# arduino.net
KiCad netlist of a schematic drawn in Altium Designer
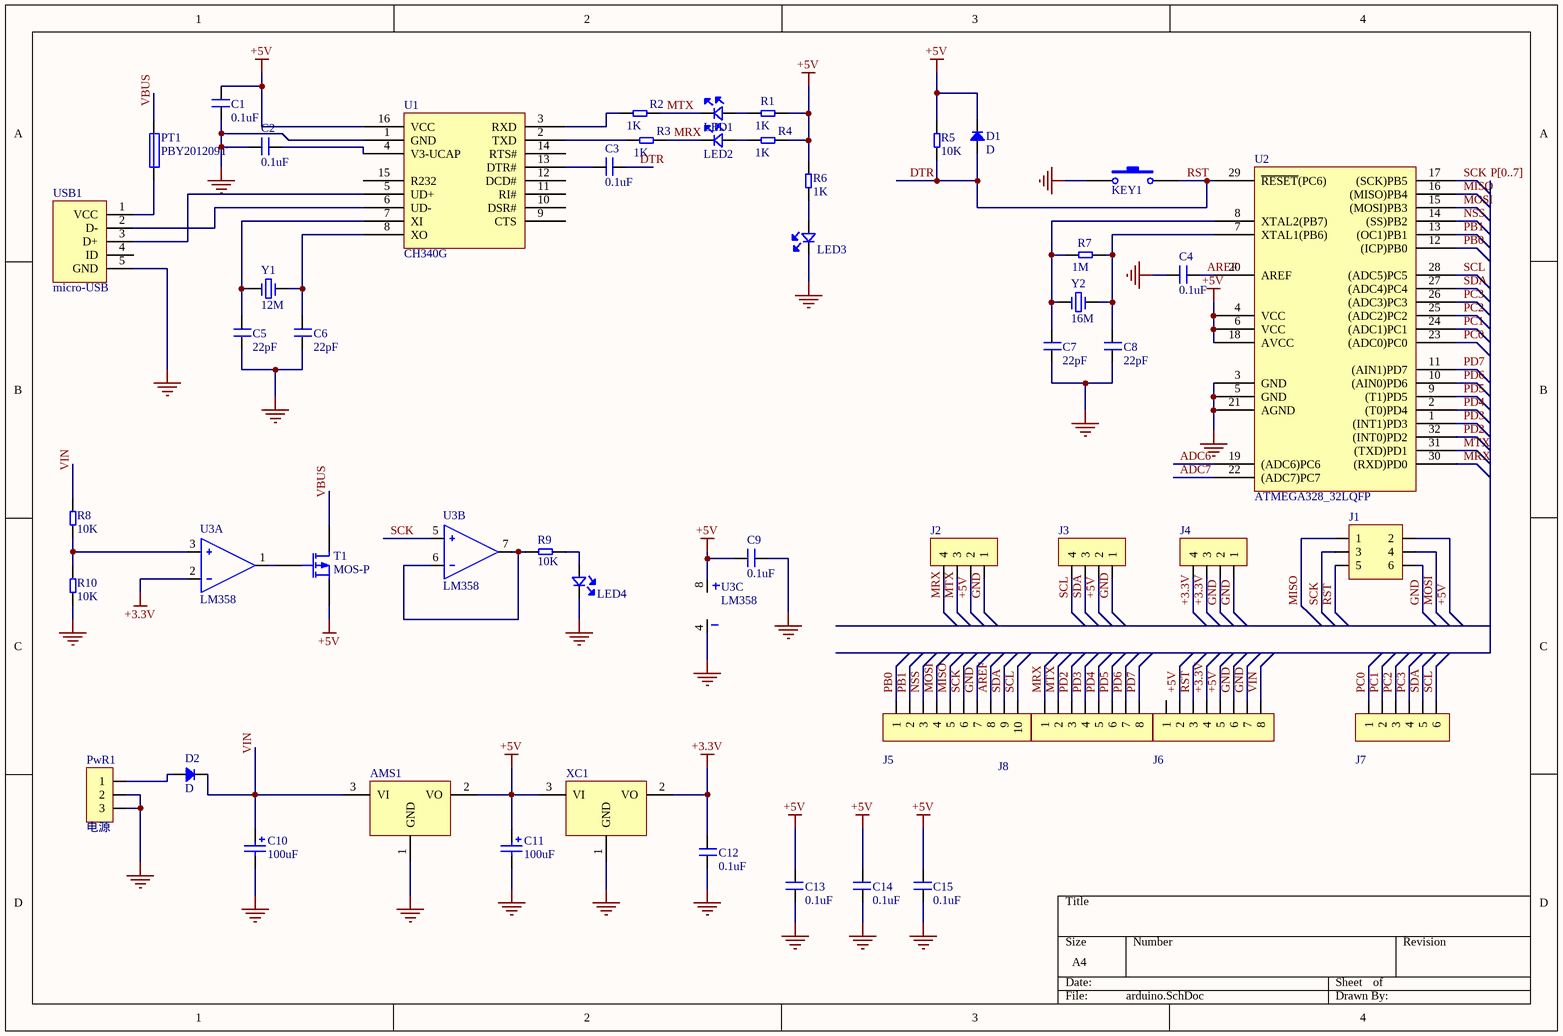
[diagram p0: arduino.SchDoc]

(export (version "E")
  (design (tool "Eeschema 10.0.6"))
  (components
    (comp (ref "AMS1")
      (value "AMS1117-5.0")
      (footprint "AMS1117-5.0")
      (libsource (lib "arduino") (part "AMS1117-5.0"))
    )
    (comp (ref "C1") (value "0.1uF") (footprint "0805C") (libsource (lib "arduino") (part "CAP")))
    (comp (ref "C2") (value "0.1uF") (footprint "0805C") (libsource (lib "arduino") (part "CAP")))
    (comp (ref "C3") (value "0.1uF") (footprint "0805C") (libsource (lib "arduino") (part "CAP")))
    (comp (ref "C4") (value "0.1uF") (footprint "0805C") (libsource (lib "arduino") (part "CAP")))
    (comp (ref "C5") (value "22pF") (footprint "0805C") (libsource (lib "arduino") (part "CAP")))
    (comp (ref "C6") (value "22pF") (footprint "0805C") (libsource (lib "arduino") (part "CAP")))
    (comp (ref "C7") (value "22pF") (footprint "0805C") (libsource (lib "arduino") (part "CAP")))
    (comp (ref "C8") (value "22pF") (footprint "0805C") (libsource (lib "arduino") (part "CAP")))
    (comp (ref "C9") (value "0.1uF") (footprint "0805C") (libsource (lib "arduino") (part "CAP")))
    (comp (ref "C10") (value "100uF") (footprint "CAP_P") (libsource (lib "arduino") (part "CAPP")))
    (comp (ref "C11") (value "100uF") (footprint "CAP_P") (libsource (lib "arduino") (part "CAPP")))
    (comp (ref "C12") (value "0.1uF") (footprint "0805C") (libsource (lib "arduino") (part "CAP")))
    (comp (ref "C13") (value "0.1uF") (footprint "0805C") (libsource (lib "arduino") (part "CAP")))
    (comp (ref "C14") (value "0.1uF") (footprint "0805C") (libsource (lib "arduino") (part "CAP")))
    (comp (ref "C15") (value "0.1uF") (footprint "0805C") (libsource (lib "arduino") (part "CAP")))
    (comp (ref "D1") (value "D") (footprint "1206D") (libsource (lib "arduino") (part "D")))
    (comp (ref "D2") (value "D") (footprint "1206D") (libsource (lib "arduino") (part "D")))
    (comp (ref "J1")
      (value "Header 2*3")
      (footprint "PIN2*3")
      (libsource (lib "arduino") (part "Header 2*3"))
    )
    (comp (ref "J2") (value "Header") (footprint "PIN4") (libsource (lib "arduino") (part "Header 4")))
    (comp (ref "J3") (value "Header") (footprint "PIN4") (libsource (lib "arduino") (part "Header 4")))
    (comp (ref "J4") (value "Header") (footprint "PIN4") (libsource (lib "arduino") (part "Header 4")))
    (comp (ref "J5") (value "Header 10") (footprint "PIN10") (libsource (lib "arduino") (part "Header 10")))
    (comp (ref "J6") (value "Header 8") (footprint "PIN8") (libsource (lib "arduino") (part "Header 8")))
    (comp (ref "J7") (value "Header 6") (footprint "PIN6") (libsource (lib "arduino") (part "Header 6")))
    (comp (ref "J8") (value "Header 8") (footprint "PIN8") (libsource (lib "arduino") (part "Header 8")))
    (comp (ref "KEY1") (value "KEY") (footprint "KEY") (libsource (lib "arduino") (part "KEY")))
    (comp (ref "LED1") (value "LED") (footprint "0805L") (libsource (lib "arduino") (part "LED")))
    (comp (ref "LED2") (value "LED") (footprint "0805L") (libsource (lib "arduino") (part "LED")))
    (comp (ref "LED3") (value "LED") (footprint "0805L") (libsource (lib "arduino") (part "LED")))
    (comp (ref "LED4") (value "LED") (footprint "0805L") (libsource (lib "arduino") (part "LED")))
    (comp (ref "PT1") (value "PBY201209T") (footprint "PT") (libsource (lib "arduino") (part "PT")))
    (comp (ref "PwR1") (value "电源") (footprint "DC005") (libsource (lib "arduino") (part "PwR")))
    (comp (ref "R1") (value "1K") (footprint "0805R") (libsource (lib "arduino") (part "RES")))
    (comp (ref "R2") (value "1K") (footprint "0805R") (libsource (lib "arduino") (part "RES")))
    (comp (ref "R3") (value "1K") (footprint "0805R") (libsource (lib "arduino") (part "RES")))
    (comp (ref "R4") (value "1K") (footprint "0805R") (libsource (lib "arduino") (part "RES")))
    (comp (ref "R5") (value "10K") (footprint "0805R") (libsource (lib "arduino") (part "RES")))
    (comp (ref "R6") (value "1K") (footprint "0805R") (libsource (lib "arduino") (part "RES")))
    (comp (ref "R7") (value "1M") (footprint "0805R") (libsource (lib "arduino") (part "RES")))
    (comp (ref "R8") (value "10K") (footprint "0805R") (libsource (lib "arduino") (part "RES")))
    (comp (ref "R9") (value "10K") (footprint "0805R") (libsource (lib "arduino") (part "RES")))
    (comp (ref "R10") (value "10K") (footprint "0805R") (libsource (lib "arduino") (part "RES")))
    (comp (ref "T1") (value "MOS-P") (footprint "SI2301") (libsource (lib "arduino") (part "MOS-P")))
    (comp (ref "U1") (value "CH340G") (footprint "CH340G") (libsource (lib "arduino") (part "CH340G")))
    (comp (ref "U2")
      (value "ATMEGA328_32LQFP")
      (footprint "ATMEGA328P-AU")
      (libsource (lib "arduino") (part "ATMEGA328_32LQFP"))
    )
    (comp (ref "U3") (value "LM358") (footprint "LM358") (libsource (lib "arduino") (part "LM358")))
    (comp (ref "USB1")
      (value "micro-USB")
      (footprint "micro-usb")
      (libsource (lib "arduino") (part "micro-USB"))
    )
    (comp (ref "XC1")
      (value "XC6206P332")
      (footprint "XC626P332")
      (libsource (lib "arduino") (part "XC6206P332"))
    )
    (comp (ref "Y1") (value "12M") (footprint "CRYSTAL") (libsource (lib "arduino") (part "CRYSTAL")))
    (comp (ref "Y2") (value "16M") (footprint "CRYSTAL") (libsource (lib "arduino") (part "CRYSTAL")))
  )
  (nets
    (net (code "9") (name "+3.3V") (class "Default")
      (node (ref "C12") (pin "1") (pinfunction "1_1") (pintype "passive"))
      (node (ref "J4") (pin "3") (pinfunction "3_3") (pintype "passive"))
      (node (ref "J4") (pin "4") (pinfunction "4_4") (pintype "passive"))
      (node (ref "J6") (pin "4") (pinfunction "4_4") (pintype "passive"))
      (node (ref "U3") (pin "2") (pinfunction "2_2") (pintype "passive"))
      (node (ref "XC1") (pin "2") (pinfunction "VO_2") (pintype "passive"))
    )
    (net (code "10") (name "+5V") (class "Default")
      (node (ref "AMS1") (pin "2") (pinfunction "VO_2") (pintype "passive"))
      (node (ref "C1") (pin "2") (pinfunction "2_2") (pintype "passive"))
      (node (ref "C11") (pin "1") (pinfunction "1_1") (pintype "passive"))
      (node (ref "C13") (pin "2") (pinfunction "2_2") (pintype "passive"))
      (node (ref "C14") (pin "2") (pinfunction "2_2") (pintype "passive"))
      (node (ref "C15") (pin "2") (pinfunction "2_2") (pintype "passive"))
      (node (ref "C9") (pin "1") (pinfunction "1_1") (pintype "passive"))
      (node (ref "D1") (pin "1") (pinfunction "1_1") (pintype "passive"))
      (node (ref "J1") (pin "2") (pinfunction "2_2") (pintype "passive"))
      (node (ref "J2") (pin "2") (pinfunction "2_2") (pintype "passive"))
      (node (ref "J3") (pin "2") (pinfunction "2_2") (pintype "passive"))
      (node (ref "J6") (pin "2") (pinfunction "2_2") (pintype "passive"))
      (node (ref "J6") (pin "5") (pinfunction "5_5") (pintype "passive"))
      (node (ref "R1") (pin "2") (pinfunction "2_2") (pintype "passive"))
      (node (ref "R4") (pin "2") (pinfunction "2_2") (pintype "passive"))
      (node (ref "R5") (pin "2") (pinfunction "2_2") (pintype "passive"))
      (node (ref "R6") (pin "2") (pinfunction "2_2") (pintype "passive"))
      (node (ref "T1") (pin "2") (pinfunction "S_2") (pintype "passive"))
      (node (ref "U1") (pin "16") (pinfunction "VCC_16") (pintype "passive"))
      (node (ref "U2") (pin "18") (pinfunction "AVCC_18") (pintype "passive"))
      (node (ref "U2") (pin "4") (pinfunction "VCC_4") (pintype "passive"))
      (node (ref "U2") (pin "6") (pinfunction "VCC_6") (pintype "passive"))
      (node (ref "U3") (pin "8") (pinfunction "8_8") (pintype "passive"))
      (node (ref "XC1") (pin "3") (pinfunction "VI_3") (pintype "passive"))
    )
    (net (code "11") (name "/ADC6") (class "Default")
      (node (ref "U2") (pin "19") (pinfunction "(ADC6)PC6_19") (pintype "passive"))
    )
    (net (code "12") (name "/ADC7") (class "Default")
      (node (ref "U2") (pin "22") (pinfunction "(ADC7)PC7_22") (pintype "passive"))
    )
    (net (code "13") (name "/AREF") (class "Default")
      (node (ref "C4") (pin "2") (pinfunction "2_2") (pintype "passive"))
      (node (ref "J5") (pin "8") (pinfunction "8_8") (pintype "passive"))
      (node (ref "U2") (pin "20") (pinfunction "AREF_20") (pintype "passive"))
    )
    (net (code "14") (name "/DTR") (class "Default")
      (node (ref "C3") (pin "2") (pinfunction "2_2") (pintype "passive"))
      (node (ref "D1") (pin "2") (pinfunction "2_2") (pintype "passive"))
      (node (ref "J1") (pin "5") (pinfunction "5_5") (pintype "passive"))
      (node (ref "J6") (pin "3") (pinfunction "3_3") (pintype "passive"))
      (node (ref "KEY1") (pin "2") (pinfunction "2_2") (pintype "passive"))
      (node (ref "R5") (pin "1") (pinfunction "1_1") (pintype "passive"))
      (node (ref "U2") (pin "29") (pinfunction "~{RESET}(PC6)_29") (pintype "passive"))
    )
    (net (code "15") (name "/MISO") (class "Default")
      (node (ref "J1") (pin "1") (pinfunction "1_1") (pintype "passive"))
      (node (ref "J5") (pin "5") (pinfunction "5_5") (pintype "passive"))
      (node (ref "U2") (pin "16") (pinfunction "(MISO)PB4_16") (pintype "passive"))
    )
    (net (code "16") (name "/MOSI") (class "Default")
      (node (ref "J1") (pin "4") (pinfunction "4_4") (pintype "passive"))
      (node (ref "J5") (pin "4") (pinfunction "4_4") (pintype "passive"))
      (node (ref "U2") (pin "15") (pinfunction "(MOSI)PB3_15") (pintype "passive"))
    )
    (net (code "17") (name "/MRX") (class "Default")
      (node (ref "J2") (pin "4") (pinfunction "4_4") (pintype "passive"))
      (node (ref "J8") (pin "1") (pinfunction "1_1") (pintype "passive"))
      (node (ref "LED2") (pin "2") (pinfunction "2_2") (pintype "passive"))
      (node (ref "R3") (pin "2") (pinfunction "2_2") (pintype "passive"))
      (node (ref "U2") (pin "30") (pinfunction "(RXD)PD0_30") (pintype "passive"))
    )
    (net (code "18") (name "/MTX") (class "Default")
      (node (ref "J2") (pin "3") (pinfunction "3_3") (pintype "passive"))
      (node (ref "J8") (pin "2") (pinfunction "2_2") (pintype "passive"))
      (node (ref "LED1") (pin "2") (pinfunction "2_2") (pintype "passive"))
      (node (ref "R2") (pin "2") (pinfunction "2_2") (pintype "passive"))
      (node (ref "U2") (pin "31") (pinfunction "(TXD)PD1_31") (pintype "passive"))
    )
    (net (code "19") (name "/NSS") (class "Default")
      (node (ref "J5") (pin "3") (pinfunction "3_3") (pintype "passive"))
      (node (ref "U2") (pin "14") (pinfunction "(SS)PB2_14") (pintype "passive"))
    )
    (net (code "20") (name "/PB0") (class "Default")
      (node (ref "J5") (pin "1") (pinfunction "1_1") (pintype "passive"))
      (node (ref "U2") (pin "12") (pinfunction "(ICP)PB0_12") (pintype "passive"))
    )
    (net (code "21") (name "/PB1") (class "Default")
      (node (ref "J5") (pin "2") (pinfunction "2_2") (pintype "passive"))
      (node (ref "U2") (pin "13") (pinfunction "(OC1)PB1_13") (pintype "passive"))
    )
    (net (code "22") (name "/PC0") (class "Default")
      (node (ref "J7") (pin "1") (pinfunction "1_1") (pintype "passive"))
      (node (ref "U2") (pin "23") (pinfunction "(ADC0)PC0_23") (pintype "passive"))
    )
    (net (code "23") (name "/PC1") (class "Default")
      (node (ref "J7") (pin "2") (pinfunction "2_2") (pintype "passive"))
      (node (ref "U2") (pin "24") (pinfunction "(ADC1)PC1_24") (pintype "passive"))
    )
    (net (code "24") (name "/PC2") (class "Default")
      (node (ref "J7") (pin "3") (pinfunction "3_3") (pintype "passive"))
      (node (ref "U2") (pin "25") (pinfunction "(ADC2)PC2_25") (pintype "passive"))
    )
    (net (code "25") (name "/PC3") (class "Default")
      (node (ref "J7") (pin "4") (pinfunction "4_4") (pintype "passive"))
      (node (ref "U2") (pin "26") (pinfunction "(ADC3)PC3_26") (pintype "passive"))
    )
    (net (code "26") (name "/PD2") (class "Default")
      (node (ref "J8") (pin "3") (pinfunction "3_3") (pintype "passive"))
      (node (ref "U2") (pin "32") (pinfunction "(INT0)PD2_32") (pintype "passive"))
    )
    (net (code "27") (name "/PD3") (class "Default")
      (node (ref "J8") (pin "4") (pinfunction "4_4") (pintype "passive"))
      (node (ref "U2") (pin "1") (pinfunction "(INT1)PD3_1") (pintype "passive"))
    )
    (net (code "28") (name "/PD4") (class "Default")
      (node (ref "J8") (pin "5") (pinfunction "5_5") (pintype "passive"))
      (node (ref "U2") (pin "2") (pinfunction "(T0)PD4_2") (pintype "passive"))
    )
    (net (code "29") (name "/PD5") (class "Default")
      (node (ref "J8") (pin "6") (pinfunction "6_6") (pintype "passive"))
      (node (ref "U2") (pin "9") (pinfunction "(T1)PD5_9") (pintype "passive"))
    )
    (net (code "30") (name "/PD6") (class "Default")
      (node (ref "J8") (pin "7") (pinfunction "7_7") (pintype "passive"))
      (node (ref "U2") (pin "10") (pinfunction "(AIN0)PD6_10") (pintype "passive"))
    )
    (net (code "31") (name "/PD7") (class "Default")
      (node (ref "J8") (pin "8") (pinfunction "8_8") (pintype "passive"))
      (node (ref "U2") (pin "11") (pinfunction "(AIN1)PD7_11") (pintype "passive"))
    )
    (net (code "33") (name "/SCK") (class "Default")
      (node (ref "J1") (pin "3") (pinfunction "3_3") (pintype "passive"))
      (node (ref "J5") (pin "6") (pinfunction "6_6") (pintype "passive"))
      (node (ref "U2") (pin "17") (pinfunction "(SCK)PB5_17") (pintype "passive"))
      (node (ref "U3") (pin "5") (pinfunction "5_5") (pintype "passive"))
    )
    (net (code "34") (name "/SCL") (class "Default")
      (node (ref "J3") (pin "4") (pinfunction "4_4") (pintype "passive"))
      (node (ref "J5") (pin "10") (pinfunction "10_10") (pintype "passive"))
      (node (ref "J7") (pin "6") (pinfunction "6_6") (pintype "passive"))
      (node (ref "U2") (pin "28") (pinfunction "(ADC5)PC5_28") (pintype "passive"))
    )
    (net (code "35") (name "/SDA") (class "Default")
      (node (ref "J3") (pin "3") (pinfunction "3_3") (pintype "passive"))
      (node (ref "J5") (pin "9") (pinfunction "9_9") (pintype "passive"))
      (node (ref "J7") (pin "5") (pinfunction "5_5") (pintype "passive"))
      (node (ref "U2") (pin "27") (pinfunction "(ADC4)PC4_27") (pintype "passive"))
    )
    (net (code "36") (name "/VBUS") (class "Default")
      (node (ref "PT1") (pin "2") (pinfunction "2_2") (pintype "passive"))
      (node (ref "T1") (pin "3") (pinfunction "D_3") (pintype "passive"))
    )
    (net (code "37") (name "/VIN") (class "Default")
      (node (ref "AMS1") (pin "3") (pinfunction "VI_3") (pintype "passive"))
      (node (ref "C10") (pin "1") (pinfunction "1_1") (pintype "passive"))
      (node (ref "D2") (pin "1") (pinfunction "1_1") (pintype "passive"))
      (node (ref "J6") (pin "8") (pinfunction "8_8") (pintype "passive"))
      (node (ref "R8") (pin "2") (pinfunction "2_2") (pintype "passive"))
    )
    (net (code "38") (name "GND") (class "Default")
      (node (ref "AMS1") (pin "1") (pinfunction "GND_1") (pintype "passive"))
      (node (ref "C1") (pin "1") (pinfunction "1_1") (pintype "passive"))
      (node (ref "C10") (pin "2") (pinfunction "2_2") (pintype "passive"))
      (node (ref "C11") (pin "2") (pinfunction "2_2") (pintype "passive"))
      (node (ref "C12") (pin "2") (pinfunction "2_2") (pintype "passive"))
      (node (ref "C13") (pin "1") (pinfunction "1_1") (pintype "passive"))
      (node (ref "C14") (pin "1") (pinfunction "1_1") (pintype "passive"))
      (node (ref "C15") (pin "1") (pinfunction "1_1") (pintype "passive"))
      (node (ref "C2") (pin "1") (pinfunction "1_1") (pintype "passive"))
      (node (ref "C4") (pin "1") (pinfunction "1_1") (pintype "passive"))
      (node (ref "C5") (pin "2") (pinfunction "2_2") (pintype "passive"))
      (node (ref "C6") (pin "2") (pinfunction "2_2") (pintype "passive"))
      (node (ref "C7") (pin "2") (pinfunction "2_2") (pintype "passive"))
      (node (ref "C8") (pin "2") (pinfunction "2_2") (pintype "passive"))
      (node (ref "C9") (pin "2") (pinfunction "2_2") (pintype "passive"))
      (node (ref "J1") (pin "6") (pinfunction "6_6") (pintype "passive"))
      (node (ref "J2") (pin "1") (pinfunction "1_1") (pintype "passive"))
      (node (ref "J3") (pin "1") (pinfunction "1_1") (pintype "passive"))
      (node (ref "J4") (pin "1") (pinfunction "1_1") (pintype "passive"))
      (node (ref "J4") (pin "2") (pinfunction "2_2") (pintype "passive"))
      (node (ref "J5") (pin "7") (pinfunction "7_7") (pintype "passive"))
      (node (ref "J6") (pin "6") (pinfunction "6_6") (pintype "passive"))
      (node (ref "J6") (pin "7") (pinfunction "7_7") (pintype "passive"))
      (node (ref "KEY1") (pin "3") (pinfunction "3_3") (pintype "passive"))
      (node (ref "LED3") (pin "2") (pinfunction "2_2") (pintype "passive"))
      (node (ref "LED4") (pin "2") (pinfunction "2_2") (pintype "passive"))
      (node (ref "PwR1") (pin "2") (pinfunction "2_2") (pintype "passive"))
      (node (ref "PwR1") (pin "3") (pinfunction "3_3") (pintype "passive"))
      (node (ref "R10") (pin "1") (pinfunction "1_1") (pintype "passive"))
      (node (ref "U1") (pin "1") (pinfunction "GND_1") (pintype "passive"))
      (node (ref "U2") (pin "21") (pinfunction "AGND_21") (pintype "passive"))
      (node (ref "U2") (pin "3") (pinfunction "GND_3") (pintype "passive"))
      (node (ref "U2") (pin "5") (pinfunction "GND_5") (pintype "passive"))
      (node (ref "U3") (pin "4") (pinfunction "4_4") (pintype "passive"))
      (node (ref "USB1") (pin "5") (pinfunction "GND_5") (pintype "passive"))
      (node (ref "XC1") (pin "1") (pinfunction "GND_1") (pintype "passive"))
    )
    (net (code "39") (name "Net-(D2-Pad2)") (class "Default")
      (node (ref "D2") (pin "2") (pinfunction "2_2") (pintype "passive"))
      (node (ref "PwR1") (pin "1") (pinfunction "1_1") (pintype "passive"))
    )
    (net (code "40") (name "Net-(LED1-Pad1)") (class "Default")
      (node (ref "LED1") (pin "1") (pinfunction "1_1") (pintype "passive"))
      (node (ref "R1") (pin "1") (pinfunction "1_1") (pintype "passive"))
    )
    (net (code "41") (name "Net-(LED2-Pad1)") (class "Default")
      (node (ref "LED2") (pin "1") (pinfunction "1_1") (pintype "passive"))
      (node (ref "R4") (pin "1") (pinfunction "1_1") (pintype "passive"))
    )
    (net (code "42") (name "Net-(LED3-Pad1)") (class "Default")
      (node (ref "LED3") (pin "1") (pinfunction "1_1") (pintype "passive"))
      (node (ref "R6") (pin "1") (pinfunction "1_1") (pintype "passive"))
    )
    (net (code "43") (name "Net-(LED4-Pad1)") (class "Default")
      (node (ref "LED4") (pin "1") (pinfunction "1_1") (pintype "passive"))
      (node (ref "R9") (pin "1") (pinfunction "1_1") (pintype "passive"))
    )
    (net (code "44") (name "Net-(R9-Pad2)") (class "Default")
      (node (ref "R9") (pin "2") (pinfunction "2_2") (pintype "passive"))
      (node (ref "U3") (pin "6") (pinfunction "6_6") (pintype "passive"))
      (node (ref "U3") (pin "7") (pinfunction "7_7") (pintype "passive"))
    )
    (net (code "45") (name "Net-(R10-Pad2)") (class "Default")
      (node (ref "R10") (pin "2") (pinfunction "2_2") (pintype "passive"))
      (node (ref "R8") (pin "1") (pinfunction "1_1") (pintype "passive"))
      (node (ref "U3") (pin "3") (pinfunction "3_3") (pintype "passive"))
    )
    (net (code "46") (name "Net-(T1-G)") (class "Default")
      (node (ref "T1") (pin "1") (pinfunction "G_1") (pintype "passive"))
      (node (ref "U3") (pin "1") (pinfunction "1_1") (pintype "passive"))
    )
    (net (code "47") (name "Net-(U1-DTR#)") (class "Default")
      (node (ref "C3") (pin "1") (pinfunction "1_1") (pintype "passive"))
      (node (ref "U1") (pin "13") (pinfunction "DTR#_13") (pintype "passive"))
    )
    (net (code "48") (name "Net-(U1-RXD)") (class "Default")
      (node (ref "R2") (pin "1") (pinfunction "1_1") (pintype "passive"))
      (node (ref "U1") (pin "3") (pinfunction "RXD_3") (pintype "passive"))
    )
    (net (code "49") (name "Net-(U1-TXD)") (class "Default")
      (node (ref "R3") (pin "1") (pinfunction "1_1") (pintype "passive"))
      (node (ref "U1") (pin "2") (pinfunction "TXD_2") (pintype "passive"))
    )
    (net (code "50") (name "Net-(U1-UD+)") (class "Default")
      (node (ref "U1") (pin "5") (pinfunction "UD+_5") (pintype "passive"))
      (node (ref "USB1") (pin "3") (pinfunction "D+_3") (pintype "passive"))
    )
    (net (code "51") (name "Net-(U1-UD-)") (class "Default")
      (node (ref "U1") (pin "6") (pinfunction "UD-_6") (pintype "passive"))
      (node (ref "USB1") (pin "2") (pinfunction "D-_2") (pintype "passive"))
    )
    (net (code "52") (name "Net-(U1-V3-UCAP)") (class "Default")
      (node (ref "C2") (pin "2") (pinfunction "2_2") (pintype "passive"))
      (node (ref "U1") (pin "4") (pinfunction "V3-UCAP_4") (pintype "passive"))
    )
    (net (code "53") (name "Net-(U1-XI)") (class "Default")
      (node (ref "C5") (pin "1") (pinfunction "1_1") (pintype "passive"))
      (node (ref "U1") (pin "7") (pinfunction "XI_7") (pintype "passive"))
      (node (ref "Y1") (pin "1") (pinfunction "1_1") (pintype "passive"))
    )
    (net (code "54") (name "Net-(U1-XO)") (class "Default")
      (node (ref "C6") (pin "1") (pinfunction "1_1") (pintype "passive"))
      (node (ref "U1") (pin "8") (pinfunction "XO_8") (pintype "passive"))
      (node (ref "Y1") (pin "2") (pinfunction "2_2") (pintype "passive"))
    )
    (net (code "55") (name "Net-(U2-XTAL1(PB6))") (class "Default")
      (node (ref "C8") (pin "1") (pinfunction "1_1") (pintype "passive"))
      (node (ref "R7") (pin "2") (pinfunction "2_2") (pintype "passive"))
      (node (ref "U2") (pin "7") (pinfunction "XTAL1(PB6)_7") (pintype "passive"))
      (node (ref "Y2") (pin "2") (pinfunction "2_2") (pintype "passive"))
    )
    (net (code "56") (name "Net-(U2-XTAL2(PB7))") (class "Default")
      (node (ref "C7") (pin "1") (pinfunction "1_1") (pintype "passive"))
      (node (ref "R7") (pin "1") (pinfunction "1_1") (pintype "passive"))
      (node (ref "U2") (pin "8") (pinfunction "XTAL2(PB7)_8") (pintype "passive"))
      (node (ref "Y2") (pin "1") (pinfunction "1_1") (pintype "passive"))
    )
    (net (code "57") (name "Net-(USB1-VCC)") (class "Default")
      (node (ref "PT1") (pin "1") (pinfunction "1_1") (pintype "passive"))
      (node (ref "USB1") (pin "1") (pinfunction "VCC_1") (pintype "passive"))
    )
    (net (code "58") (name "unconnected-(J6-Pad1)") (class "Default")
      (node (ref "J6") (pin "1") (pinfunction "1_1") (pintype "passive"))
    )
    (net (code "59") (name "unconnected-(U1-CTS-Pad9)") (class "Default")
      (node (ref "U1") (pin "9") (pinfunction "CTS_9") (pintype "passive"))
    )
    (net (code "60") (name "unconnected-(U1-DCD#-Pad12)") (class "Default")
      (node (ref "U1") (pin "12") (pinfunction "DCD#_12") (pintype "passive"))
    )
    (net (code "61") (name "unconnected-(U1-DSR#-Pad10)") (class "Default")
      (node (ref "U1") (pin "10") (pinfunction "DSR#_10") (pintype "passive"))
    )
    (net (code "62") (name "unconnected-(U1-R232-Pad15)") (class "Default")
      (node (ref "U1") (pin "15") (pinfunction "R232_15") (pintype "passive"))
    )
    (net (code "63") (name "unconnected-(U1-RI#-Pad11)") (class "Default")
      (node (ref "U1") (pin "11") (pinfunction "RI#_11") (pintype "passive"))
    )
    (net (code "64") (name "unconnected-(U1-RTS#-Pad14)") (class "Default")
      (node (ref "U1") (pin "14") (pinfunction "RTS#_14") (pintype "passive"))
    )
    (net (code "65") (name "unconnected-(USB1-ID-Pad4)") (class "Default")
      (node (ref "USB1") (pin "4") (pinfunction "ID_4") (pintype "passive"))
    )
  )
)
